# C2_B5AvaNut_R3.net
KiCad netlist of a schematic drawn in EAGLE
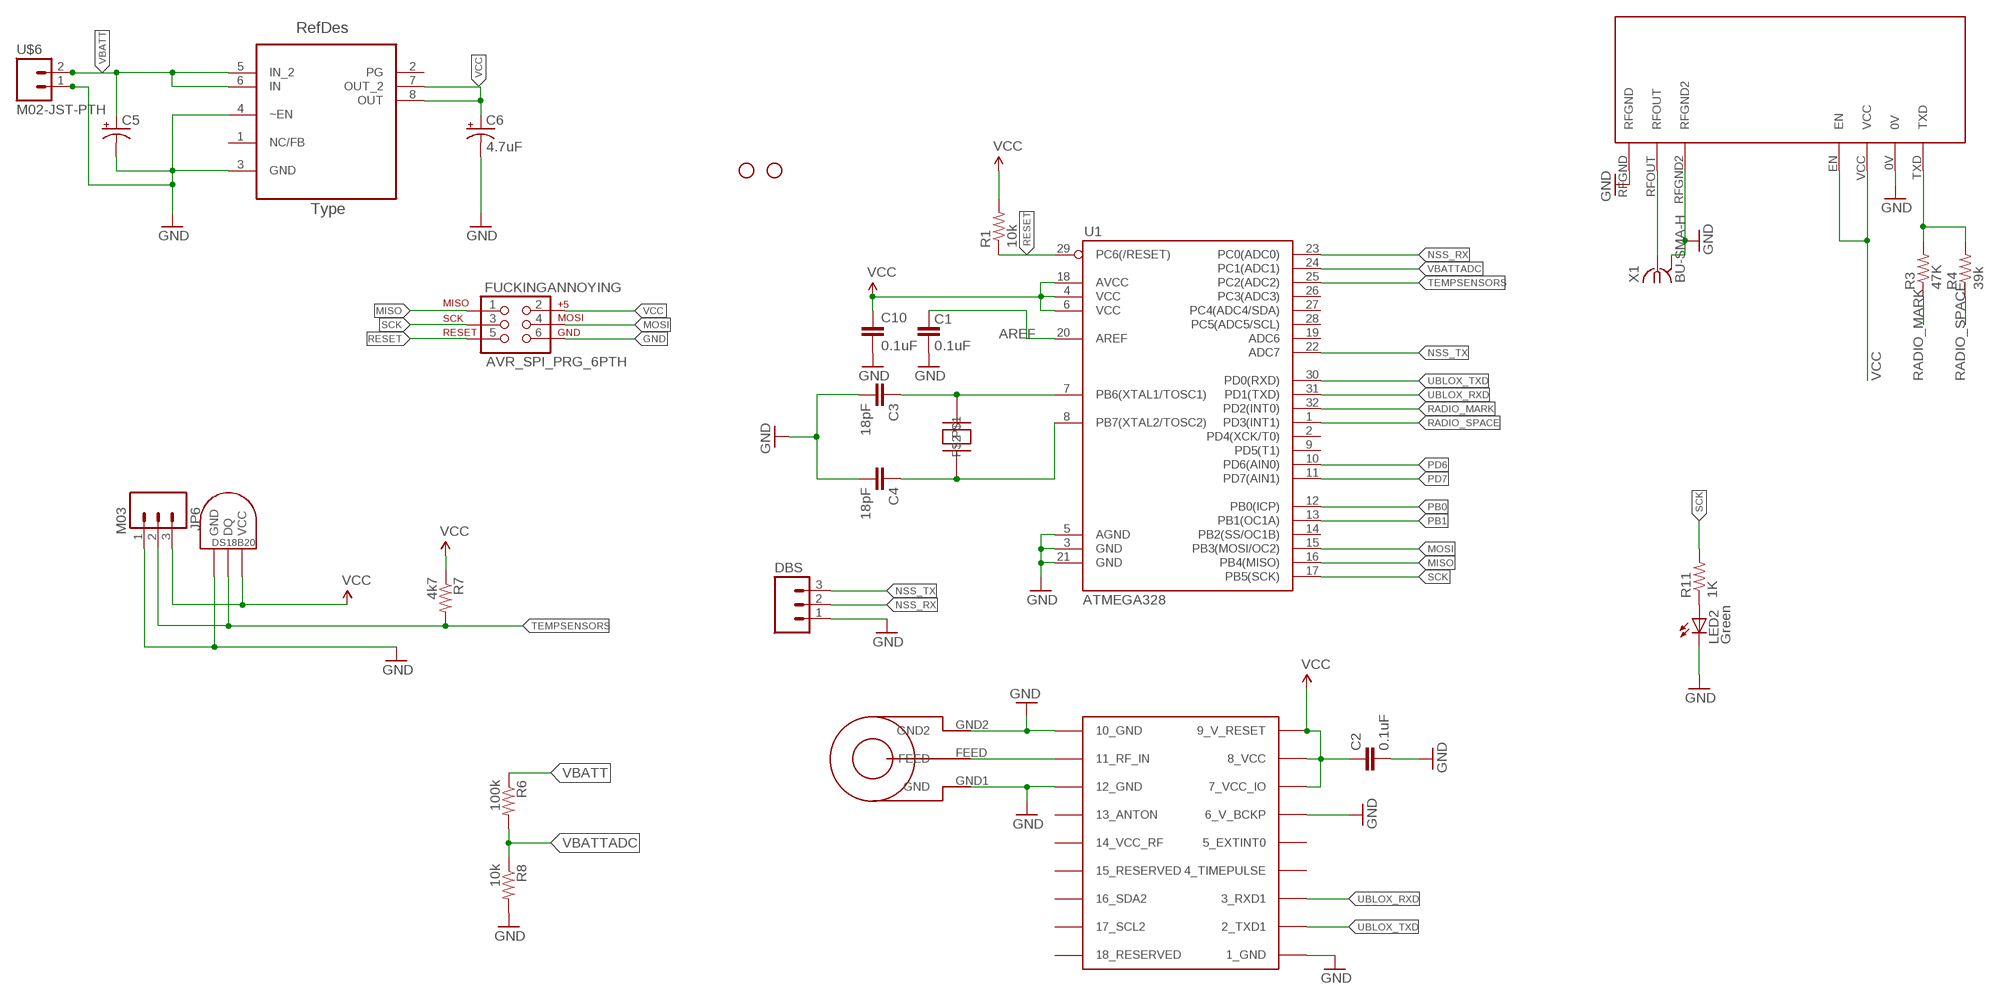
[diagram p0: schematic, sheet 1]

(export (version "E")
  (design (tool "Eeschema 10.0.6"))
  (components
    (comp (ref "C1")
      (value "0.1uF")
      (footprint "eagle-import:0603-CAP")
      (libsource (lib "eagle-import") (part "CAP0603-CAP"))
    )
    (comp (ref "C2")
      (value "0.1uF")
      (footprint "eagle-import:0603-CAP")
      (libsource (lib "eagle-import") (part "CAP0603-CAP"))
    )
    (comp (ref "C3")
      (value "18pF")
      (footprint "eagle-import:0603-CAP")
      (libsource (lib "eagle-import") (part "CAP0603-CAP"))
    )
    (comp (ref "C4")
      (value "18pF")
      (footprint "eagle-import:0603-CAP")
      (libsource (lib "eagle-import") (part "CAP0603-CAP"))
    )
    (comp (ref "C5")
      (value "CAP_POL1206-KIT")
      (footprint "eagle-import:EIA3216-KIT")
      (libsource (lib "eagle-import") (part "CAP_POL1206-KIT"))
    )
    (comp (ref "C6")
      (value "4.7uF")
      (footprint "eagle-import:EIA3216-KIT")
      (libsource (lib "eagle-import") (part "CAP_POL1206-KIT"))
    )
    (comp (ref "C10")
      (value "0.1uF")
      (footprint "eagle-import:0603-CAP")
      (libsource (lib "eagle-import") (part "CAP0603-CAP"))
    )
    (comp (ref "DBS")
      (value "M03PTH")
      (footprint "eagle-import:1X03")
      (libsource (lib "eagle-import") (part "M03PTH"))
    )
    (comp (ref "FUCKINGANNOYING")
      (value "AVR_SPI_PRG_6PTH")
      (footprint "eagle-import:2X3")
      (libsource (lib "eagle-import") (part "AVR_SPI_PRG_6PTH"))
    )
    (comp (ref "JP1")
      (value "STAND-OFF")
      (footprint "eagle-import:STAND-OFF")
      (libsource (lib "eagle-import") (part "STAND-OFF"))
    )
    (comp (ref "JP2")
      (value "STAND-OFF")
      (footprint "eagle-import:STAND-OFF")
      (libsource (lib "eagle-import") (part "STAND-OFF"))
    )
    (comp (ref "JP6")
      (value "M03")
      (footprint "eagle-import:M03-JST")
      (libsource (lib "eagle-import") (part "ava_M03"))
    )
    (comp (ref "LED2")
      (value "Green")
      (footprint "eagle-import:LED-0603")
      (libsource (lib "eagle-import") (part "LED0603"))
    )
    (comp (ref "NTX2TEMP")
      (value "DS1821")
      (footprint "eagle-import:DS18B20_SOIC")
      (libsource (lib "eagle-import") (part "DS1820SOIC"))
    )
    (comp (ref "R1")
      (value "10k")
      (footprint "eagle-import:0603-RES")
      (libsource (lib "eagle-import") (part "RESISTOR0603-RES"))
    )
    (comp (ref "R3")
      (value "47K")
      (footprint "eagle-import:0603-RES")
      (libsource (lib "eagle-import") (part "RESISTOR0603-RES"))
    )
    (comp (ref "R4")
      (value "39k")
      (footprint "eagle-import:0603-RES")
      (libsource (lib "eagle-import") (part "RESISTOR0603-RES"))
    )
    (comp (ref "R6")
      (value "100k")
      (footprint "eagle-import:0603-RES")
      (libsource (lib "eagle-import") (part "RESISTOR0603-RES"))
    )
    (comp (ref "R7")
      (value "4k7")
      (footprint "eagle-import:0603-RES")
      (libsource (lib "eagle-import") (part "RESISTOR0603-RES"))
    )
    (comp (ref "R8")
      (value "10k")
      (footprint "eagle-import:0603-RES")
      (libsource (lib "eagle-import") (part "RESISTOR0603-RES"))
    )
    (comp (ref "R11")
      (value "1K")
      (footprint "eagle-import:0603-RES")
      (libsource (lib "eagle-import") (part "RESISTOR0603-RES"))
    )
    (comp (ref "U$1")
      (value "UBLOX_MAX-6")
      (footprint "eagle-import:UBLOX_MAX-6")
      (libsource (lib "eagle-import") (part "UBLOX_MAX-6"))
    )
    (comp (ref "U$2")
      (value "ABRACON_ABM3_CRYSTAL")
      (footprint "eagle-import:ABRACON_ABM3_CRYSTAL")
      (libsource (lib "eagle-import") (part "ABRACON_ABM3_CRYSTAL"))
    )
    (comp (ref "U$3")
      (value "SARANTEL-SR1202")
      (footprint "eagle-import:SARANTEL-SR1202")
      (libsource (lib "eagle-import") (part "SARANTEL-SR1202"))
    )
    (comp (ref "U$4")
      (value "NTX2")
      (footprint "eagle-import:NTX2")
      (libsource (lib "eagle-import") (part "NTX2"))
    )
    (comp (ref "U$6")
      (value "M02-JST-PTH")
      (footprint "eagle-import:M02-JST-PTH")
      (libsource (lib "eagle-import") (part "M02-JST-PTH"))
    )
    (comp (ref "U1")
      (value "ATMEGA328")
      (footprint "eagle-import:TQFP32-08")
      (libsource (lib "eagle-import") (part "ATMEGA168"))
    )
    (comp (ref "U2")
      (value "TPS76633D")
      (footprint "eagle-import:SOIC127P600X175-8N")
      (libsource (lib "eagle-import") (part "TPS76633D"))
    )
    (comp (ref "X1")
      (value "BU-SMA-H")
      (footprint "eagle-import:BU-SMA-H")
      (libsource (lib "eagle-import") (part "BU-SMA-H"))
    )
  )
  (nets
    (net (code "1") (name "/AREF") (class "Default")
      (node (ref "C1") (pin "2") (pinfunction "2_2") (pintype "passive"))
      (node (ref "U1") (pin "20") (pinfunction "AREF_20") (pintype "bidirectional"))
    )
    (net (code "2") (name "GND") (class "Default")
      (node (ref "C1") (pin "1") (pinfunction "1_1") (pintype "passive"))
      (node (ref "C10") (pin "2") (pinfunction "2_2") (pintype "passive"))
      (node (ref "C2") (pin "2") (pinfunction "2_2") (pintype "passive"))
      (node (ref "C3") (pin "2") (pinfunction "2_2") (pintype "passive"))
      (node (ref "C4") (pin "2") (pinfunction "2_2") (pintype "passive"))
      (node (ref "C5") (pin "C") (pinfunction "-_C") (pintype "passive"))
      (node (ref "C6") (pin "C") (pinfunction "-_C") (pintype "passive"))
      (node (ref "DBS") (pin "1") (pinfunction "1_1") (pintype "passive"))
      (node (ref "FUCKINGANNOYING") (pin "6") (pinfunction "6_6") (pintype "passive"))
      (node (ref "JP6") (pin "1") (pinfunction "1_1") (pintype "passive"))
      (node (ref "LED2") (pin "C") (pinfunction "C_C") (pintype "passive"))
      (node (ref "NTX2TEMP") (pin "GND") (pinfunction "GND_GND") (pintype "power_in"))
      (node (ref "R8") (pin "2") (pinfunction "2_2") (pintype "passive"))
      (node (ref "U$1") (pin "10_GND") (pinfunction "10_GND_10_GND") (pintype "bidirectional"))
      (node (ref "U$1") (pin "12_GND") (pinfunction "12_GND_12_GND") (pintype "bidirectional"))
      (node (ref "U$1") (pin "1_GND") (pinfunction "1_GND_1_GND") (pintype "bidirectional"))
      (node (ref "U$1") (pin "6_V_BCKP") (pinfunction "6_V_BCKP_6_V_BCKP") (pintype "bidirectional"))
      (node (ref "U$3") (pin "GND1") (pinfunction "GND_GND1") (pintype "bidirectional"))
      (node (ref "U$3") (pin "GND2") (pinfunction "GND2_GND2") (pintype "bidirectional"))
      (node (ref "U$4") (pin "0V") (pinfunction "0V_0V") (pintype "bidirectional"))
      (node (ref "U$4") (pin "RFGND") (pinfunction "RFGND_RFGND") (pintype "bidirectional"))
      (node (ref "U$4") (pin "RFGND2") (pinfunction "RFGND2_RFGND2") (pintype "bidirectional"))
      (node (ref "U$6") (pin "1") (pinfunction "1_1") (pintype "passive"))
      (node (ref "U1") (pin "21") (pinfunction "GND_21") (pintype "bidirectional"))
      (node (ref "U1") (pin "3") (pinfunction "GND_3") (pintype "bidirectional"))
      (node (ref "U1") (pin "5") (pinfunction "AGND_5") (pintype "bidirectional"))
      (node (ref "U2") (pin "3") (pinfunction "GND_3") (pintype "passive"))
      (node (ref "U2") (pin "4") (pinfunction "~{EN}_4") (pintype "input"))
      (node (ref "X1") (pin "2") (pinfunction "GND_2") (pintype "power_in"))
    )
    (net (code "3") (name "MISO") (class "Default")
      (node (ref "FUCKINGANNOYING") (pin "1") (pinfunction "1_1") (pintype "passive"))
      (node (ref "U1") (pin "16") (pinfunction "PB4(MISO)_16") (pintype "bidirectional"))
    )
    (net (code "4") (name "MOSI") (class "Default")
      (node (ref "FUCKINGANNOYING") (pin "4") (pinfunction "4_4") (pintype "passive"))
      (node (ref "U1") (pin "15") (pinfunction "PB3(MOSI/OC2)_15") (pintype "bidirectional"))
    )
    (net (code "5") (name "NSS_RX") (class "Default")
      (node (ref "DBS") (pin "2") (pinfunction "2_2") (pintype "passive"))
      (node (ref "U1") (pin "23") (pinfunction "PC0(ADC0)_23") (pintype "bidirectional"))
    )
    (net (code "6") (name "NSS_TX") (class "Default")
      (node (ref "DBS") (pin "3") (pinfunction "3_3") (pintype "passive"))
      (node (ref "U1") (pin "22") (pinfunction "ADC7_22") (pintype "bidirectional"))
    )
    (net (code "7") (name "Net-(LED2-PadA)") (class "Default")
      (node (ref "LED2") (pin "A") (pinfunction "A_A") (pintype "passive"))
      (node (ref "R11") (pin "1") (pinfunction "1_1") (pintype "passive"))
    )
    (net (code "8") (name "Net-(R3-Pad2)") (class "Default")
      (node (ref "R3") (pin "2") (pinfunction "2_2") (pintype "passive"))
      (node (ref "R4") (pin "2") (pinfunction "2_2") (pintype "passive"))
      (node (ref "U$4") (pin "TXD") (pinfunction "TXD_TXD") (pintype "bidirectional"))
    )
    (net (code "9") (name "Net-(U$1-Pad11_RF_IN)") (class "Default")
      (node (ref "U$1") (pin "11_RF_IN") (pinfunction "11_RF_IN_11_RF_IN") (pintype "bidirectional"))
      (node (ref "U$3") (pin "FEED") (pinfunction "FEED_FEED") (pintype "bidirectional"))
    )
    (net (code "10") (name "Net-(U$4-PadRFOUT)") (class "Default")
      (node (ref "U$4") (pin "RFOUT") (pinfunction "RFOUT_RFOUT") (pintype "bidirectional"))
      (node (ref "X1") (pin "1") (pinfunction "1_1") (pintype "passive"))
    )
    (net (code "11") (name "Net-(U1-PB6(XTAL1{slash}TOSC1))") (class "Default")
      (node (ref "C3") (pin "1") (pinfunction "1_1") (pintype "passive"))
      (node (ref "U$2") (pin "P$2") (pinfunction "P$2_P$2") (pintype "bidirectional"))
      (node (ref "U1") (pin "7") (pinfunction "PB6(XTAL1/TOSC1)_7") (pintype "bidirectional"))
    )
    (net (code "12") (name "Net-(U1-PB7(XTAL2{slash}TOSC2))") (class "Default")
      (node (ref "C4") (pin "1") (pinfunction "1_1") (pintype "passive"))
      (node (ref "U$2") (pin "P$1") (pinfunction "P$1_P$1") (pintype "bidirectional"))
      (node (ref "U1") (pin "8") (pinfunction "PB7(XTAL2/TOSC2)_8") (pintype "bidirectional"))
    )
    (net (code "13") (name "PB0") (class "Default")
      (node (ref "U1") (pin "12") (pinfunction "PB0(ICP)_12") (pintype "bidirectional"))
    )
    (net (code "14") (name "PB1") (class "Default")
      (node (ref "U1") (pin "13") (pinfunction "PB1(OC1A)_13") (pintype "bidirectional"))
    )
    (net (code "15") (name "PD6") (class "Default")
      (node (ref "U1") (pin "10") (pinfunction "PD6(AIN0)_10") (pintype "bidirectional"))
    )
    (net (code "16") (name "PD7") (class "Default")
      (node (ref "U1") (pin "11") (pinfunction "PD7(AIN1)_11") (pintype "bidirectional"))
    )
    (net (code "17") (name "RADIO_MARK") (class "Default")
      (node (ref "R3") (pin "1") (pinfunction "1_1") (pintype "passive"))
      (node (ref "U1") (pin "32") (pinfunction "PD2(INT0)_32") (pintype "bidirectional"))
    )
    (net (code "18") (name "RADIO_SPACE") (class "Default")
      (node (ref "R4") (pin "1") (pinfunction "1_1") (pintype "passive"))
      (node (ref "U1") (pin "1") (pinfunction "PD3(INT1)_1") (pintype "bidirectional"))
    )
    (net (code "19") (name "RESET") (class "Default")
      (node (ref "FUCKINGANNOYING") (pin "5") (pinfunction "5_5") (pintype "passive"))
      (node (ref "R1") (pin "1") (pinfunction "1_1") (pintype "passive"))
      (node (ref "U1") (pin "29") (pinfunction "PC6(/RESET)_29") (pintype "bidirectional"))
    )
    (net (code "20") (name "SCK") (class "Default")
      (node (ref "FUCKINGANNOYING") (pin "3") (pinfunction "3_3") (pintype "passive"))
      (node (ref "R11") (pin "2") (pinfunction "2_2") (pintype "passive"))
      (node (ref "U1") (pin "17") (pinfunction "PB5(SCK)_17") (pintype "bidirectional"))
    )
    (net (code "21") (name "TEMPSENSORS") (class "Default")
      (node (ref "JP6") (pin "2") (pinfunction "2_2") (pintype "passive"))
      (node (ref "NTX2TEMP") (pin "DQ") (pinfunction "DQ_DQ") (pintype "bidirectional"))
      (node (ref "R7") (pin "2") (pinfunction "2_2") (pintype "passive"))
      (node (ref "U1") (pin "25") (pinfunction "PC2(ADC2)_25") (pintype "bidirectional"))
    )
    (net (code "22") (name "UBLOX_RXD") (class "Default")
      (node (ref "U$1") (pin "3_RXD1") (pinfunction "3_RXD1_3_RXD1") (pintype "bidirectional"))
      (node (ref "U1") (pin "31") (pinfunction "PD1(TXD)_31") (pintype "bidirectional"))
    )
    (net (code "23") (name "UBLOX_TXD") (class "Default")
      (node (ref "U$1") (pin "2_TXD1") (pinfunction "2_TXD1_2_TXD1") (pintype "bidirectional"))
      (node (ref "U1") (pin "30") (pinfunction "PD0(RXD)_30") (pintype "bidirectional"))
    )
    (net (code "24") (name "VBATT") (class "Default")
      (node (ref "C5") (pin "A") (pinfunction "+_A") (pintype "passive"))
      (node (ref "R6") (pin "1") (pinfunction "1_1") (pintype "passive"))
      (node (ref "U$6") (pin "2") (pinfunction "2_2") (pintype "passive"))
      (node (ref "U2") (pin "5") (pinfunction "IN_2_5") (pintype "input"))
      (node (ref "U2") (pin "6") (pinfunction "IN_6") (pintype "input"))
    )
    (net (code "25") (name "VBATTADC") (class "Default")
      (node (ref "R6") (pin "2") (pinfunction "2_2") (pintype "passive"))
      (node (ref "R8") (pin "1") (pinfunction "1_1") (pintype "passive"))
      (node (ref "U1") (pin "24") (pinfunction "PC1(ADC1)_24") (pintype "bidirectional"))
    )
    (net (code "26") (name "VCC") (class "Default")
      (node (ref "C10") (pin "1") (pinfunction "1_1") (pintype "passive"))
      (node (ref "C2") (pin "1") (pinfunction "1_1") (pintype "passive"))
      (node (ref "C6") (pin "A") (pinfunction "+_A") (pintype "passive"))
      (node (ref "FUCKINGANNOYING") (pin "2") (pinfunction "2_2") (pintype "passive"))
      (node (ref "JP6") (pin "3") (pinfunction "3_3") (pintype "passive"))
      (node (ref "NTX2TEMP") (pin "VCC") (pinfunction "VCC_VCC") (pintype "power_in"))
      (node (ref "R1") (pin "2") (pinfunction "2_2") (pintype "passive"))
      (node (ref "R7") (pin "1") (pinfunction "1_1") (pintype "passive"))
      (node (ref "U$1") (pin "7_VCC_IO") (pinfunction "7_VCC_IO_7_VCC_IO") (pintype "bidirectional"))
      (node (ref "U$1") (pin "8_VCC") (pinfunction "8_VCC_8_VCC") (pintype "bidirectional"))
      (node (ref "U$1") (pin "9_V_RESET") (pinfunction "9_V_RESET_9_V_RESET") (pintype "bidirectional"))
      (node (ref "U$4") (pin "EN") (pinfunction "EN_EN") (pintype "bidirectional"))
      (node (ref "U$4") (pin "VCC") (pinfunction "VCC_VCC") (pintype "bidirectional"))
      (node (ref "U1") (pin "18") (pinfunction "AVCC_18") (pintype "bidirectional"))
      (node (ref "U1") (pin "4") (pinfunction "VCC_4") (pintype "bidirectional"))
      (node (ref "U1") (pin "6") (pinfunction "VCC_6") (pintype "bidirectional"))
      (node (ref "U2") (pin "7") (pinfunction "OUT_2_7") (pintype "output"))
      (node (ref "U2") (pin "8") (pinfunction "OUT_8") (pintype "output"))
    )
    (net (code "27") (name "unconnected-(U$1-Pad4_TIMEPULSE)") (class "Default")
      (node (ref "U$1") (pin "4_TIMEPULSE") (pinfunction "4_TIMEPULSE_4_TIMEPULSE") (pintype "bidirectional"))
    )
    (net (code "28") (name "unconnected-(U$1-Pad5_EXTINT0)") (class "Default")
      (node (ref "U$1") (pin "5_EXTINT0") (pinfunction "5_EXTINT0_5_EXTINT0") (pintype "bidirectional"))
    )
    (net (code "29") (name "unconnected-(U$1-Pad13_ANTON)") (class "Default")
      (node (ref "U$1") (pin "13_ANTON") (pinfunction "13_ANTON_13_ANTON") (pintype "bidirectional"))
    )
    (net (code "30") (name "unconnected-(U$1-Pad14_VCC_RF)") (class "Default")
      (node (ref "U$1") (pin "14_VCC_RF") (pinfunction "14_VCC_RF_14_VCC_RF") (pintype "bidirectional"))
    )
    (net (code "31") (name "unconnected-(U$1-Pad15_RESERVED)") (class "Default")
      (node (ref "U$1") (pin "15_RESERVED") (pinfunction "15_RESERVED_15_RESERVED") (pintype "bidirectional"))
    )
    (net (code "32") (name "unconnected-(U$1-Pad16_SDA2)") (class "Default")
      (node (ref "U$1") (pin "16_SDA2") (pinfunction "16_SDA2_16_SDA2") (pintype "bidirectional"))
    )
    (net (code "33") (name "unconnected-(U$1-Pad17_SCL2)") (class "Default")
      (node (ref "U$1") (pin "17_SCL2") (pinfunction "17_SCL2_17_SCL2") (pintype "bidirectional"))
    )
    (net (code "34") (name "unconnected-(U$1-Pad18_RESERVED)") (class "Default")
      (node (ref "U$1") (pin "18_RESERVED") (pinfunction "18_RESERVED_18_RESERVED") (pintype "bidirectional"))
    )
    (net (code "35") (name "unconnected-(U1-ADC6-Pad19)") (class "Default")
      (node (ref "U1") (pin "19") (pinfunction "ADC6_19") (pintype "bidirectional"))
    )
    (net (code "36") (name "unconnected-(U1-PB2(SS{slash}OC1B)-Pad14)") (class "Default")
      (node (ref "U1") (pin "14") (pinfunction "PB2(SS/OC1B)_14") (pintype "bidirectional"))
    )
    (net (code "37") (name "unconnected-(U1-PC3(ADC3)-Pad26)") (class "Default")
      (node (ref "U1") (pin "26") (pinfunction "PC3(ADC3)_26") (pintype "bidirectional"))
    )
    (net (code "38") (name "unconnected-(U1-PC4(ADC4{slash}SDA)-Pad27)") (class "Default")
      (node (ref "U1") (pin "27") (pinfunction "PC4(ADC4/SDA)_27") (pintype "bidirectional"))
    )
    (net (code "39") (name "unconnected-(U1-PC5(ADC5{slash}SCL)-Pad28)") (class "Default")
      (node (ref "U1") (pin "28") (pinfunction "PC5(ADC5/SCL)_28") (pintype "bidirectional"))
    )
    (net (code "40") (name "unconnected-(U1-PD4(XCK{slash}T0)-Pad2)") (class "Default")
      (node (ref "U1") (pin "2") (pinfunction "PD4(XCK/T0)_2") (pintype "bidirectional"))
    )
    (net (code "41") (name "unconnected-(U1-PD5(T1)-Pad9)") (class "Default")
      (node (ref "U1") (pin "9") (pinfunction "PD5(T1)_9") (pintype "bidirectional"))
    )
    (net (code "42") (name "unconnected-(U2-NC{slash}FB-Pad1)") (class "Default")
      (node (ref "U2") (pin "1") (pinfunction "NC/FB_1") (pintype "no_connect"))
    )
    (net (code "43") (name "unconnected-(U2-PG-Pad2)") (class "Default")
      (node (ref "U2") (pin "2") (pinfunction "PG_2") (pintype "output"))
    )
  )
)
